# Rocket_End.net
KiCad netlist of a schematic drawn in EAGLE
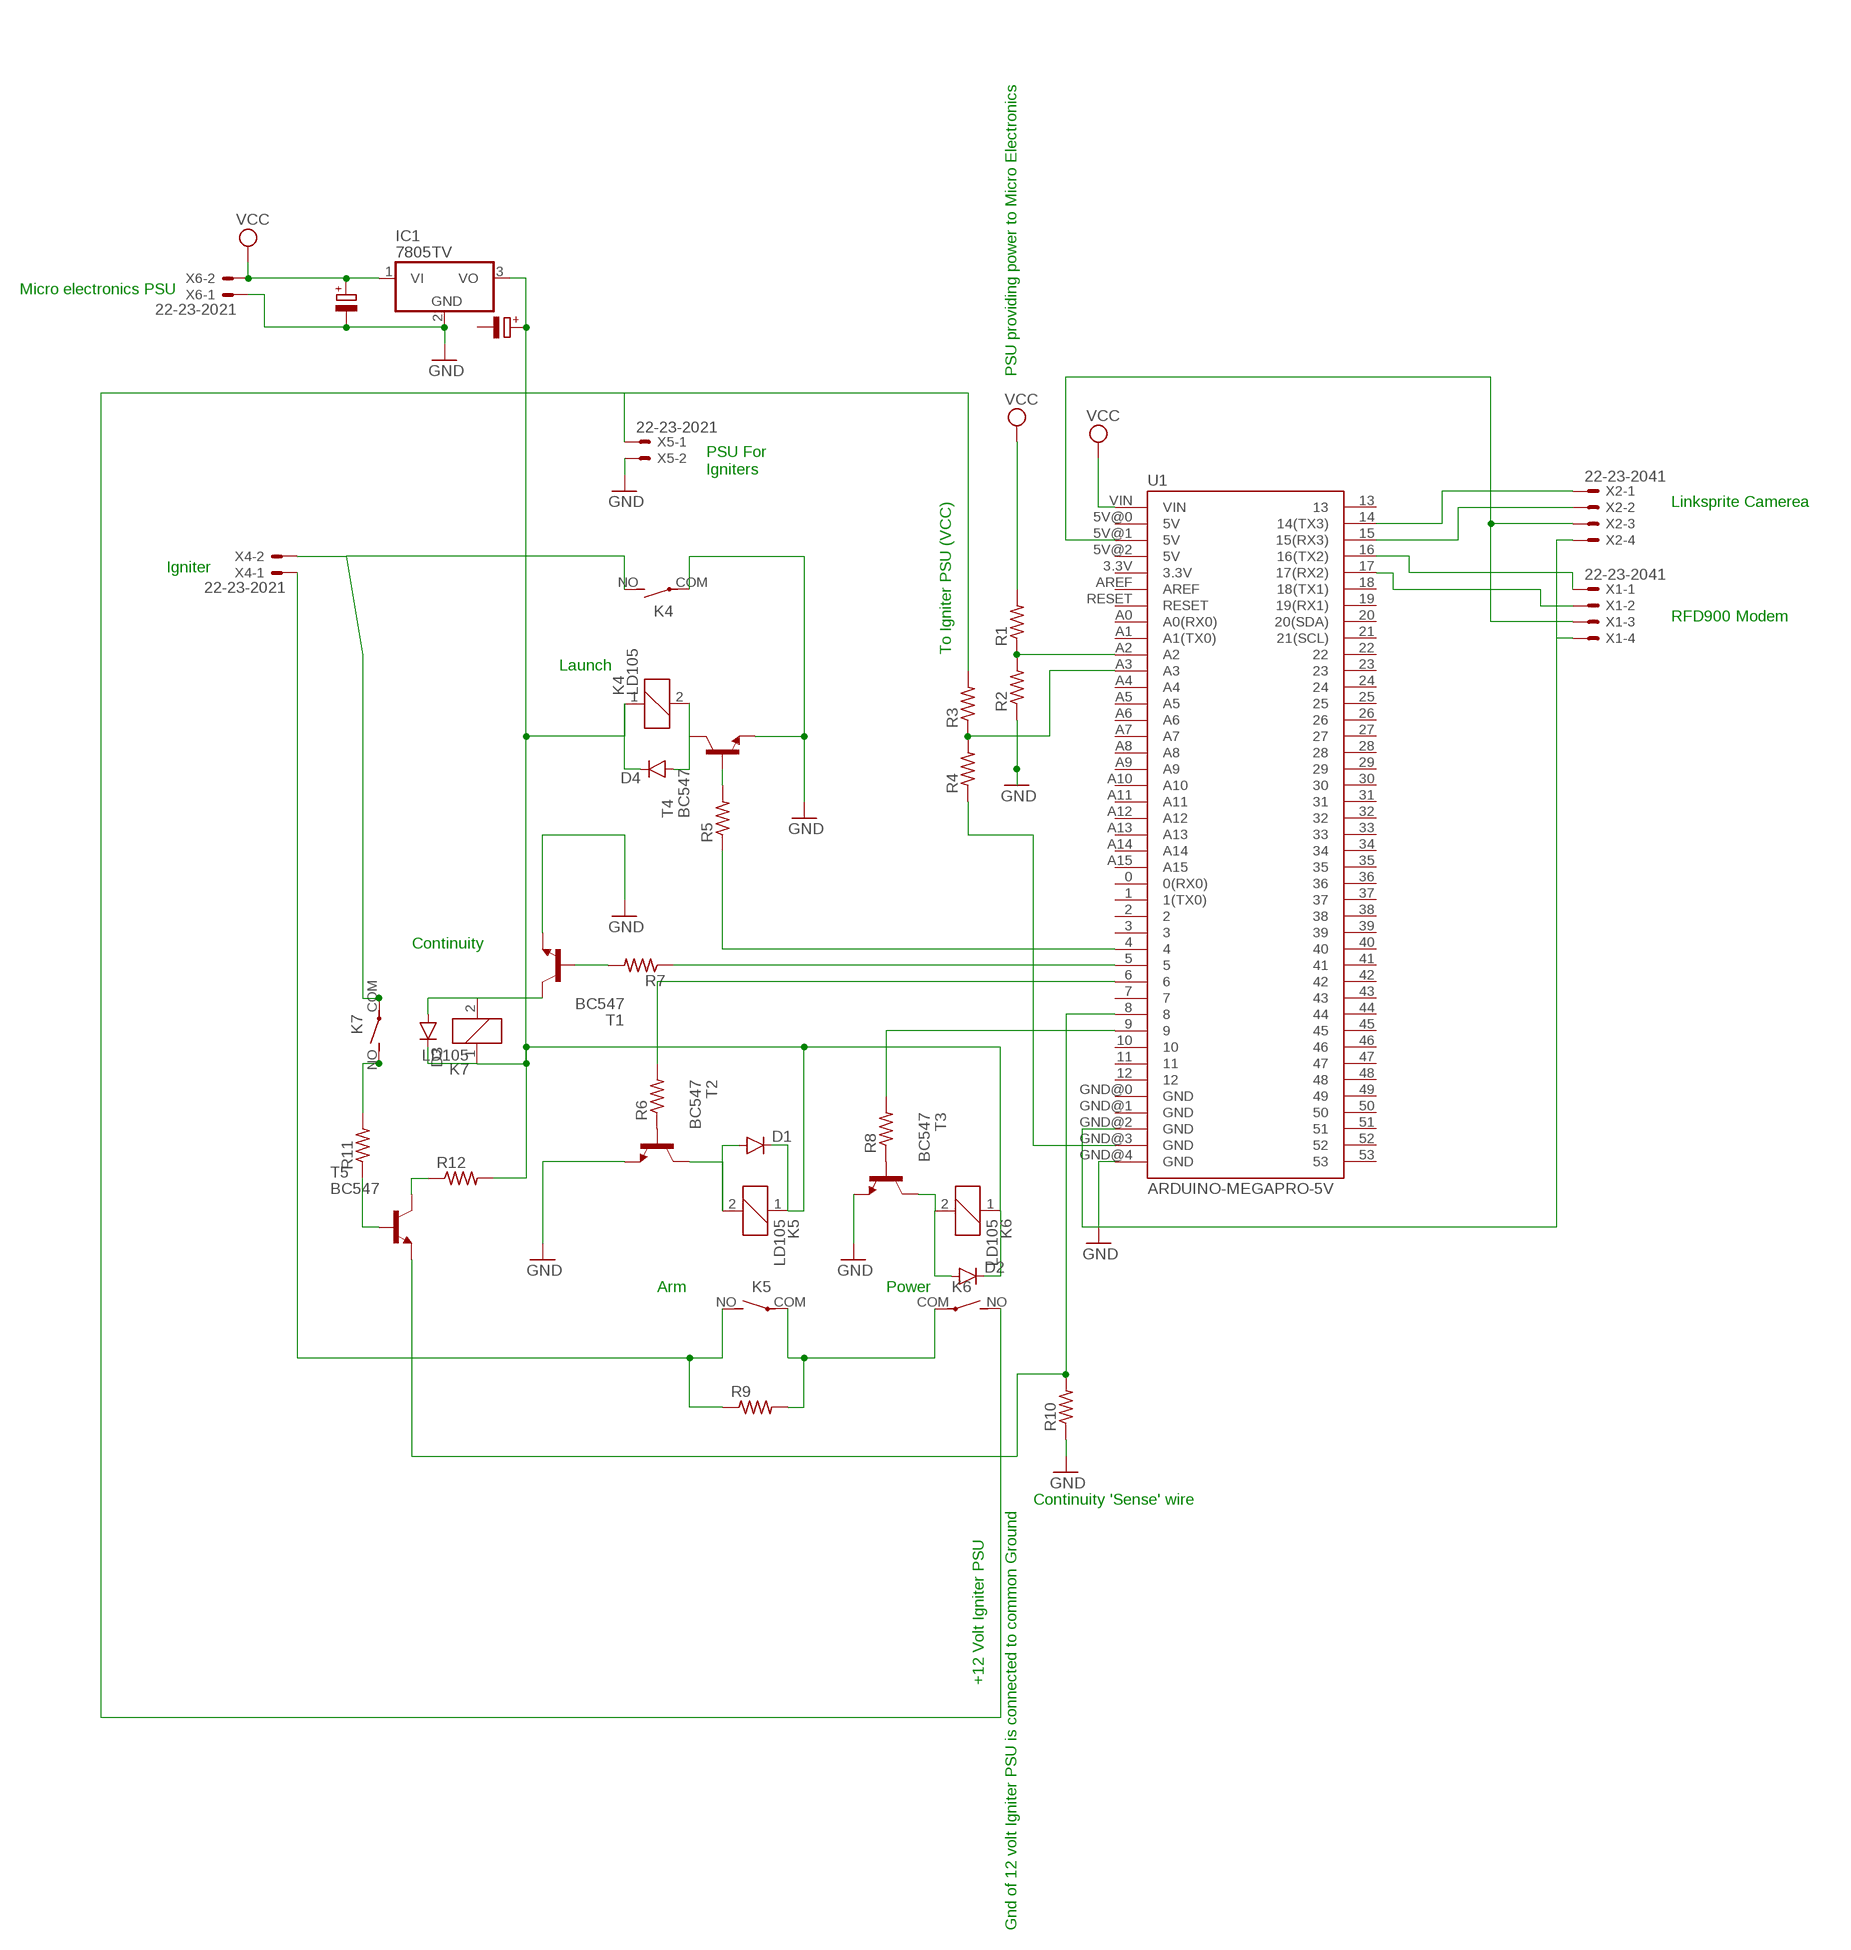
[diagram p0: schematic, sheet 1]

(export (version "E")
  (design (tool "Eeschema 10.0.6"))
  (components
    (comp (ref "D1")
      (value "DIODE1N4148")
      (footprint "eagle-import:DIODE-1N4148")
      (libsource (lib "eagle-import") (part "DIODE1N4148"))
    )
    (comp (ref "D2")
      (value "DIODE1N4148")
      (footprint "eagle-import:DIODE-1N4148")
      (libsource (lib "eagle-import") (part "DIODE1N4148"))
    )
    (comp (ref "D3")
      (value "DIODE1N4148")
      (footprint "eagle-import:DIODE-1N4148")
      (libsource (lib "eagle-import") (part "DIODE1N4148"))
    )
    (comp (ref "D4")
      (value "DIODE1N4148")
      (footprint "eagle-import:DIODE-1N4148")
      (libsource (lib "eagle-import") (part "DIODE1N4148"))
    )
    (comp (ref "IC1")
      (value "7805TV")
      (footprint "eagle-import:TO220V")
      (libsource (lib "eagle-import") (part "78TV05"))
    )
    (comp (ref "K4")
      (value "LD105")
      (footprint "eagle-import:LD")
      (libsource (lib "eagle-import") (part "LD?105"))
    )
    (comp (ref "K5")
      (value "LD105")
      (footprint "eagle-import:LD")
      (libsource (lib "eagle-import") (part "LD?105"))
    )
    (comp (ref "K6")
      (value "LD105")
      (footprint "eagle-import:LD")
      (libsource (lib "eagle-import") (part "LD?105"))
    )
    (comp (ref "K7")
      (value "LD105")
      (footprint "eagle-import:LD")
      (libsource (lib "eagle-import") (part "LD?105"))
    )
    (comp (ref "R1")
      (value "R-US_0204/7")
      (footprint "eagle-import:0204_7")
      (libsource (lib "eagle-import") (part "R-US_0204/7"))
    )
    (comp (ref "R2")
      (value "R-US_0204/7")
      (footprint "eagle-import:0204_7")
      (libsource (lib "eagle-import") (part "R-US_0204/7"))
    )
    (comp (ref "R3")
      (value "R-US_0204/7")
      (footprint "eagle-import:0204_7")
      (libsource (lib "eagle-import") (part "R-US_0204/7"))
    )
    (comp (ref "R4")
      (value "R-US_0204/7")
      (footprint "eagle-import:0204_7")
      (libsource (lib "eagle-import") (part "R-US_0204/7"))
    )
    (comp (ref "R5")
      (value "R-US_0204/7")
      (footprint "eagle-import:0204_7")
      (libsource (lib "eagle-import") (part "resistor_R-US_0204/7"))
    )
    (comp (ref "R6")
      (value "R-US_0204/7")
      (footprint "eagle-import:0204_7")
      (libsource (lib "eagle-import") (part "resistor_R-US_0204/7"))
    )
    (comp (ref "R7")
      (value "R-US_0204/7")
      (footprint "eagle-import:0204_7")
      (libsource (lib "eagle-import") (part "resistor_R-US_0204/7"))
    )
    (comp (ref "R8")
      (value "R-US_0204/7")
      (footprint "eagle-import:0204_7")
      (libsource (lib "eagle-import") (part "resistor_R-US_0204/7"))
    )
    (comp (ref "R9")
      (value "R-US_0204/7")
      (footprint "eagle-import:0204_7")
      (libsource (lib "eagle-import") (part "R-US_0204/7"))
    )
    (comp (ref "R10")
      (value "R-US_0207/7")
      (footprint "eagle-import:0207_7")
      (libsource (lib "eagle-import") (part "resistor_R-US_0207/7"))
    )
    (comp (ref "R11")
      (value "R-US_0204/7")
      (footprint "eagle-import:0204_7")
      (libsource (lib "eagle-import") (part "R-US_0204/7"))
    )
    (comp (ref "R12")
      (value "R-US_0204/7")
      (footprint "eagle-import:0204_7")
      (libsource (lib "eagle-import") (part "resistor_R-US_0204/7"))
    )
    (comp (ref "T1")
      (value "BC547")
      (footprint "eagle-import:TO92")
      (libsource (lib "eagle-import") (part "transistor-neu-to92_BC547"))
    )
    (comp (ref "T2")
      (value "BC547")
      (footprint "eagle-import:TO92")
      (libsource (lib "eagle-import") (part "transistor-neu-to92_BC547"))
    )
    (comp (ref "T3")
      (value "BC547")
      (footprint "eagle-import:TO92")
      (libsource (lib "eagle-import") (part "transistor-neu-to92_BC547"))
    )
    (comp (ref "T4")
      (value "BC547")
      (footprint "eagle-import:TO92")
      (libsource (lib "eagle-import") (part "transistor-neu-to92_BC547"))
    )
    (comp (ref "T5")
      (value "BC547")
      (footprint "eagle-import:TO92")
      (libsource (lib "eagle-import") (part "BC547"))
    )
    (comp (ref "U1")
      (value "ARDUINO-MEGAPRO-5V")
      (footprint "eagle-import:ARDUINO_MEGA-PRO-5V")
      (libsource (lib "eagle-import") (part "ARDUINO-MEGAPRO-5V"))
    )
    (comp (ref "X1")
      (value "22-23-2041")
      (footprint "eagle-import:22-23-2041")
      (fields (field (name "MF") "MOLEX"))
      (libsource (lib "eagle-import") (part "22-23-2041"))
    )
    (comp (ref "X2")
      (value "22-23-2041")
      (footprint "eagle-import:22-23-2041")
      (fields (field (name "MF") "MOLEX"))
      (libsource (lib "eagle-import") (part "22-23-2041"))
    )
    (comp (ref "X4")
      (value "22-23-2021")
      (footprint "eagle-import:22-23-2021")
      (fields (field (name "MF") "MOLEX"))
      (libsource (lib "eagle-import") (part "22-23-2021"))
    )
    (comp (ref "X5")
      (value "22-23-2021")
      (footprint "eagle-import:22-23-2021")
      (fields (field (name "MF") "MOLEX"))
      (libsource (lib "eagle-import") (part "22-23-2021"))
    )
    (comp (ref "X6")
      (value "22-23-2021")
      (footprint "eagle-import:22-23-2021")
      (fields (field (name "MF") "MOLEX"))
      (libsource (lib "eagle-import") (part "22-23-2021"))
    )
  )
  (nets
    (net (code "1") (name "GND") (class "Default")
      (node (ref "IC1") (pin "2") (pinfunction "GND_2") (pintype "passive"))
      (node (ref "K4") (pin "COM") (pinfunction "P_COM") (pintype "passive"))
      (node (ref "R10") (pin "1") (pinfunction "1_1") (pintype "passive"))
      (node (ref "R2") (pin "1") (pinfunction "1_1") (pintype "passive"))
      (node (ref "T1") (pin "1") (pinfunction "E_1") (pintype "passive"))
      (node (ref "T2") (pin "1") (pinfunction "E_1") (pintype "passive"))
      (node (ref "T3") (pin "1") (pinfunction "E_1") (pintype "passive"))
      (node (ref "T4") (pin "1") (pinfunction "E_1") (pintype "passive"))
      (node (ref "U1") (pin "GND@4") (pinfunction "GND_GND@4") (pintype "bidirectional"))
      (node (ref "X5") (pin "2") (pinfunction "S_2") (pintype "passive"))
      (node (ref "X6") (pin "1") (pinfunction "S_1") (pintype "passive"))
    )
    (net (code "2") (name "Net-(IC1-VO)") (class "Default")
      (node (ref "D1") (pin "C") (pinfunction "C_C") (pintype "passive"))
      (node (ref "D2") (pin "C") (pinfunction "C_C") (pintype "passive"))
      (node (ref "D3") (pin "C") (pinfunction "C_C") (pintype "passive"))
      (node (ref "D4") (pin "C") (pinfunction "C_C") (pintype "passive"))
      (node (ref "IC1") (pin "3") (pinfunction "VO_3") (pintype "passive"))
      (node (ref "K4") (pin "1") (pinfunction "1_1") (pintype "passive"))
      (node (ref "K5") (pin "1") (pinfunction "1_1") (pintype "passive"))
      (node (ref "K6") (pin "1") (pinfunction "1_1") (pintype "passive"))
      (node (ref "K7") (pin "1") (pinfunction "1_1") (pintype "passive"))
      (node (ref "R12") (pin "2") (pinfunction "2_2") (pintype "passive"))
    )
    (net (code "3") (name "Net-(K4B-S)") (class "Default")
      (node (ref "K4") (pin "NO") (pinfunction "S_NO") (pintype "passive"))
      (node (ref "K7") (pin "COM") (pinfunction "P_COM") (pintype "passive"))
      (node (ref "X4") (pin "2") (pinfunction "S_2") (pintype "passive"))
    )
    (net (code "4") (name "Net-(K5B-P)") (class "Default")
      (node (ref "K5") (pin "COM") (pinfunction "P_COM") (pintype "passive"))
      (node (ref "K6") (pin "COM") (pinfunction "P_COM") (pintype "passive"))
      (node (ref "R9") (pin "2") (pinfunction "2_2") (pintype "passive"))
    )
    (net (code "5") (name "Net-(K5B-S)") (class "Default")
      (node (ref "K5") (pin "NO") (pinfunction "S_NO") (pintype "passive"))
      (node (ref "R9") (pin "1") (pinfunction "1_1") (pintype "passive"))
      (node (ref "X4") (pin "1") (pinfunction "S_1") (pintype "passive"))
    )
    (net (code "6") (name "Net-(K6B-S)") (class "Default")
      (node (ref "K6") (pin "NO") (pinfunction "S_NO") (pintype "passive"))
      (node (ref "R3") (pin "2") (pinfunction "2_2") (pintype "passive"))
      (node (ref "X5") (pin "1") (pinfunction "S_1") (pintype "passive"))
    )
    (net (code "7") (name "Net-(K7B-S)") (class "Default")
      (node (ref "K7") (pin "NO") (pinfunction "S_NO") (pintype "passive"))
      (node (ref "R11") (pin "2") (pinfunction "2_2") (pintype "passive"))
    )
    (net (code "8") (name "Net-(R1-Pad1)") (class "Default")
      (node (ref "R1") (pin "1") (pinfunction "1_1") (pintype "passive"))
      (node (ref "R2") (pin "2") (pinfunction "2_2") (pintype "passive"))
      (node (ref "U1") (pin "A2") (pinfunction "A2_A2") (pintype "bidirectional"))
    )
    (net (code "9") (name "Net-(R3-Pad1)") (class "Default")
      (node (ref "R3") (pin "1") (pinfunction "1_1") (pintype "passive"))
      (node (ref "R4") (pin "2") (pinfunction "2_2") (pintype "passive"))
      (node (ref "U1") (pin "A3") (pinfunction "A3_A3") (pintype "bidirectional"))
    )
    (net (code "10") (name "Net-(R4-Pad1)") (class "Default")
      (node (ref "R4") (pin "1") (pinfunction "1_1") (pintype "passive"))
      (node (ref "U1") (pin "GND@3") (pinfunction "GND_GND@3") (pintype "bidirectional"))
    )
    (net (code "11") (name "Net-(R5-Pad1)") (class "Default")
      (node (ref "R5") (pin "1") (pinfunction "1_1") (pintype "passive"))
      (node (ref "U1") (pin "4") (pinfunction "4_4") (pintype "bidirectional"))
    )
    (net (code "12") (name "Net-(R6-Pad2)") (class "Default")
      (node (ref "R6") (pin "2") (pinfunction "2_2") (pintype "passive"))
      (node (ref "U1") (pin "6") (pinfunction "6_6") (pintype "bidirectional"))
    )
    (net (code "13") (name "Net-(R7-Pad1)") (class "Default")
      (node (ref "R7") (pin "1") (pinfunction "1_1") (pintype "passive"))
      (node (ref "U1") (pin "5") (pinfunction "5_5") (pintype "bidirectional"))
    )
    (net (code "14") (name "Net-(R8-Pad2)") (class "Default")
      (node (ref "R8") (pin "2") (pinfunction "2_2") (pintype "passive"))
      (node (ref "U1") (pin "9") (pinfunction "9_9") (pintype "bidirectional"))
    )
    (net (code "15") (name "Net-(T1-B)") (class "Default")
      (node (ref "R7") (pin "2") (pinfunction "2_2") (pintype "passive"))
      (node (ref "T1") (pin "2") (pinfunction "B_2") (pintype "passive"))
    )
    (net (code "16") (name "Net-(T1-C)") (class "Default")
      (node (ref "D3") (pin "A") (pinfunction "A_A") (pintype "passive"))
      (node (ref "K7") (pin "2") (pinfunction "2_2") (pintype "passive"))
      (node (ref "T1") (pin "3") (pinfunction "C_3") (pintype "passive"))
    )
    (net (code "17") (name "Net-(T2-B)") (class "Default")
      (node (ref "R6") (pin "1") (pinfunction "1_1") (pintype "passive"))
      (node (ref "T2") (pin "2") (pinfunction "B_2") (pintype "passive"))
    )
    (net (code "18") (name "Net-(T2-C)") (class "Default")
      (node (ref "D1") (pin "A") (pinfunction "A_A") (pintype "passive"))
      (node (ref "K5") (pin "2") (pinfunction "2_2") (pintype "passive"))
      (node (ref "T2") (pin "3") (pinfunction "C_3") (pintype "passive"))
    )
    (net (code "19") (name "Net-(T3-B)") (class "Default")
      (node (ref "R8") (pin "1") (pinfunction "1_1") (pintype "passive"))
      (node (ref "T3") (pin "2") (pinfunction "B_2") (pintype "passive"))
    )
    (net (code "20") (name "Net-(T3-C)") (class "Default")
      (node (ref "D2") (pin "A") (pinfunction "A_A") (pintype "passive"))
      (node (ref "K6") (pin "2") (pinfunction "2_2") (pintype "passive"))
      (node (ref "T3") (pin "3") (pinfunction "C_3") (pintype "passive"))
    )
    (net (code "21") (name "Net-(T4-B)") (class "Default")
      (node (ref "R5") (pin "2") (pinfunction "2_2") (pintype "passive"))
      (node (ref "T4") (pin "2") (pinfunction "B_2") (pintype "passive"))
    )
    (net (code "22") (name "Net-(T4-C)") (class "Default")
      (node (ref "D4") (pin "A") (pinfunction "A_A") (pintype "passive"))
      (node (ref "K4") (pin "2") (pinfunction "2_2") (pintype "passive"))
      (node (ref "T4") (pin "3") (pinfunction "C_3") (pintype "passive"))
    )
    (net (code "23") (name "Net-(T5-B)") (class "Default")
      (node (ref "R11") (pin "1") (pinfunction "1_1") (pintype "passive"))
      (node (ref "T5") (pin "2") (pinfunction "B_2") (pintype "passive"))
    )
    (net (code "24") (name "Net-(T5-C)") (class "Default")
      (node (ref "R12") (pin "1") (pinfunction "1_1") (pintype "passive"))
      (node (ref "T5") (pin "3") (pinfunction "C_3") (pintype "passive"))
    )
    (net (code "25") (name "Net-(T5-E)") (class "Default")
      (node (ref "R10") (pin "2") (pinfunction "2_2") (pintype "passive"))
      (node (ref "T5") (pin "1") (pinfunction "E_1") (pintype "passive"))
      (node (ref "U1") (pin "8") (pinfunction "8_8") (pintype "bidirectional"))
    )
    (net (code "26") (name "Net-(U1-14(TX3))") (class "Default")
      (node (ref "U1") (pin "14") (pinfunction "14(TX3)_14") (pintype "bidirectional"))
      (node (ref "X2") (pin "1") (pinfunction "S_1") (pintype "passive"))
    )
    (net (code "27") (name "Net-(U1-15(RX3))") (class "Default")
      (node (ref "U1") (pin "15") (pinfunction "15(RX3)_15") (pintype "bidirectional"))
      (node (ref "X2") (pin "2") (pinfunction "S_2") (pintype "passive"))
    )
    (net (code "28") (name "Net-(U1-16(TX2))") (class "Default")
      (node (ref "U1") (pin "16") (pinfunction "16(TX2)_16") (pintype "bidirectional"))
      (node (ref "X1") (pin "1") (pinfunction "S_1") (pintype "passive"))
    )
    (net (code "29") (name "Net-(U1-17(RX2))") (class "Default")
      (node (ref "U1") (pin "17") (pinfunction "17(RX2)_17") (pintype "bidirectional"))
      (node (ref "X1") (pin "2") (pinfunction "S_2") (pintype "passive"))
    )
    (net (code "30") (name "Net-(X1C-S)") (class "Default")
      (node (ref "U1") (pin "5V@1") (pinfunction "5V_5V@1") (pintype "bidirectional"))
      (node (ref "X1") (pin "3") (pinfunction "S_3") (pintype "passive"))
      (node (ref "X2") (pin "3") (pinfunction "S_3") (pintype "passive"))
    )
    (net (code "31") (name "Net-(X1D-S)") (class "Default")
      (node (ref "U1") (pin "GND@2") (pinfunction "GND_GND@2") (pintype "bidirectional"))
      (node (ref "X1") (pin "4") (pinfunction "S_4") (pintype "passive"))
      (node (ref "X2") (pin "4") (pinfunction "S_4") (pintype "passive"))
    )
    (net (code "32") (name "VCC") (class "Default")
      (node (ref "IC1") (pin "1") (pinfunction "VI_1") (pintype "input"))
      (node (ref "R1") (pin "2") (pinfunction "2_2") (pintype "passive"))
      (node (ref "U1") (pin "VIN") (pinfunction "VIN_VIN") (pintype "bidirectional"))
      (node (ref "X6") (pin "2") (pinfunction "S_2") (pintype "passive"))
    )
    (net (code "33") (name "unconnected-(U1-0(RX0)-Pad0)") (class "Default")
      (node (ref "U1") (pin "0") (pinfunction "0(RX0)_0") (pintype "bidirectional"))
    )
    (net (code "34") (name "unconnected-(U1-1(TX0)-Pad1)") (class "Default")
      (node (ref "U1") (pin "1") (pinfunction "1(TX0)_1") (pintype "bidirectional"))
    )
    (net (code "35") (name "unconnected-(U1-5V-Pad5V@0)") (class "Default")
      (node (ref "U1") (pin "5V@0") (pinfunction "5V_5V@0") (pintype "bidirectional"))
    )
    (net (code "36") (name "unconnected-(U1-5V-Pad5V@2)") (class "Default")
      (node (ref "U1") (pin "5V@2") (pinfunction "5V_5V@2") (pintype "bidirectional"))
    )
    (net (code "37") (name "unconnected-(U1-18(TX1)-Pad18)") (class "Default")
      (node (ref "U1") (pin "18") (pinfunction "18(TX1)_18") (pintype "bidirectional"))
    )
    (net (code "38") (name "unconnected-(U1-19(RX1)-Pad19)") (class "Default")
      (node (ref "U1") (pin "19") (pinfunction "19(RX1)_19") (pintype "bidirectional"))
    )
    (net (code "39") (name "unconnected-(U1-20(SDA)-Pad20)") (class "Default")
      (node (ref "U1") (pin "20") (pinfunction "20(SDA)_20") (pintype "bidirectional"))
    )
    (net (code "40") (name "unconnected-(U1-21(SCL)-Pad21)") (class "Default")
      (node (ref "U1") (pin "21") (pinfunction "21(SCL)_21") (pintype "bidirectional"))
    )
    (net (code "41") (name "unconnected-(U1-A0(RX0)-PadA0)") (class "Default")
      (node (ref "U1") (pin "A0") (pinfunction "A0(RX0)_A0") (pintype "bidirectional"))
    )
    (net (code "42") (name "unconnected-(U1-A1(TX0)-PadA1)") (class "Default")
      (node (ref "U1") (pin "A1") (pinfunction "A1(TX0)_A1") (pintype "bidirectional"))
    )
    (net (code "43") (name "unconnected-(U1-GND-PadGND@0)") (class "Default")
      (node (ref "U1") (pin "GND@0") (pinfunction "GND_GND@0") (pintype "bidirectional"))
    )
    (net (code "44") (name "unconnected-(U1-GND-PadGND@1)") (class "Default")
      (node (ref "U1") (pin "GND@1") (pinfunction "GND_GND@1") (pintype "bidirectional"))
    )
    (net (code "45") (name "unconnected-(U1-Pad2)") (class "Default")
      (node (ref "U1") (pin "2") (pinfunction "2_2") (pintype "bidirectional"))
    )
    (net (code "46") (name "unconnected-(U1-Pad3)") (class "Default")
      (node (ref "U1") (pin "3") (pinfunction "3_3") (pintype "bidirectional"))
    )
    (net (code "47") (name "unconnected-(U1-Pad3.3V)") (class "Default")
      (node (ref "U1") (pin "3.3V") (pinfunction "3.3V_3.3V") (pintype "bidirectional"))
    )
    (net (code "48") (name "unconnected-(U1-Pad7)") (class "Default")
      (node (ref "U1") (pin "7") (pinfunction "7_7") (pintype "bidirectional"))
    )
    (net (code "49") (name "unconnected-(U1-Pad10)") (class "Default")
      (node (ref "U1") (pin "10") (pinfunction "10_10") (pintype "bidirectional"))
    )
    (net (code "50") (name "unconnected-(U1-Pad11)") (class "Default")
      (node (ref "U1") (pin "11") (pinfunction "11_11") (pintype "bidirectional"))
    )
    (net (code "51") (name "unconnected-(U1-Pad12)") (class "Default")
      (node (ref "U1") (pin "12") (pinfunction "12_12") (pintype "bidirectional"))
    )
    (net (code "52") (name "unconnected-(U1-Pad13)") (class "Default")
      (node (ref "U1") (pin "13") (pinfunction "13_13") (pintype "bidirectional"))
    )
    (net (code "53") (name "unconnected-(U1-Pad22)") (class "Default")
      (node (ref "U1") (pin "22") (pinfunction "22_22") (pintype "bidirectional"))
    )
    (net (code "54") (name "unconnected-(U1-Pad23)") (class "Default")
      (node (ref "U1") (pin "23") (pinfunction "23_23") (pintype "bidirectional"))
    )
    (net (code "55") (name "unconnected-(U1-Pad24)") (class "Default")
      (node (ref "U1") (pin "24") (pinfunction "24_24") (pintype "bidirectional"))
    )
    (net (code "56") (name "unconnected-(U1-Pad25)") (class "Default")
      (node (ref "U1") (pin "25") (pinfunction "25_25") (pintype "bidirectional"))
    )
    (net (code "57") (name "unconnected-(U1-Pad26)") (class "Default")
      (node (ref "U1") (pin "26") (pinfunction "26_26") (pintype "bidirectional"))
    )
    (net (code "58") (name "unconnected-(U1-Pad27)") (class "Default")
      (node (ref "U1") (pin "27") (pinfunction "27_27") (pintype "bidirectional"))
    )
    (net (code "59") (name "unconnected-(U1-Pad28)") (class "Default")
      (node (ref "U1") (pin "28") (pinfunction "28_28") (pintype "bidirectional"))
    )
    (net (code "60") (name "unconnected-(U1-Pad29)") (class "Default")
      (node (ref "U1") (pin "29") (pinfunction "29_29") (pintype "bidirectional"))
    )
    (net (code "61") (name "unconnected-(U1-Pad30)") (class "Default")
      (node (ref "U1") (pin "30") (pinfunction "30_30") (pintype "bidirectional"))
    )
    (net (code "62") (name "unconnected-(U1-Pad31)") (class "Default")
      (node (ref "U1") (pin "31") (pinfunction "31_31") (pintype "bidirectional"))
    )
    (net (code "63") (name "unconnected-(U1-Pad32)") (class "Default")
      (node (ref "U1") (pin "32") (pinfunction "32_32") (pintype "bidirectional"))
    )
    (net (code "64") (name "unconnected-(U1-Pad33)") (class "Default")
      (node (ref "U1") (pin "33") (pinfunction "33_33") (pintype "bidirectional"))
    )
    (net (code "65") (name "unconnected-(U1-Pad34)") (class "Default")
      (node (ref "U1") (pin "34") (pinfunction "34_34") (pintype "bidirectional"))
    )
    (net (code "66") (name "unconnected-(U1-Pad35)") (class "Default")
      (node (ref "U1") (pin "35") (pinfunction "35_35") (pintype "bidirectional"))
    )
    (net (code "67") (name "unconnected-(U1-Pad36)") (class "Default")
      (node (ref "U1") (pin "36") (pinfunction "36_36") (pintype "bidirectional"))
    )
    (net (code "68") (name "unconnected-(U1-Pad37)") (class "Default")
      (node (ref "U1") (pin "37") (pinfunction "37_37") (pintype "bidirectional"))
    )
    (net (code "69") (name "unconnected-(U1-Pad38)") (class "Default")
      (node (ref "U1") (pin "38") (pinfunction "38_38") (pintype "bidirectional"))
    )
    (net (code "70") (name "unconnected-(U1-Pad39)") (class "Default")
      (node (ref "U1") (pin "39") (pinfunction "39_39") (pintype "bidirectional"))
    )
    (net (code "71") (name "unconnected-(U1-Pad40)") (class "Default")
      (node (ref "U1") (pin "40") (pinfunction "40_40") (pintype "bidirectional"))
    )
    (net (code "72") (name "unconnected-(U1-Pad41)") (class "Default")
      (node (ref "U1") (pin "41") (pinfunction "41_41") (pintype "bidirectional"))
    )
    (net (code "73") (name "unconnected-(U1-Pad42)") (class "Default")
      (node (ref "U1") (pin "42") (pinfunction "42_42") (pintype "bidirectional"))
    )
    (net (code "74") (name "unconnected-(U1-Pad43)") (class "Default")
      (node (ref "U1") (pin "43") (pinfunction "43_43") (pintype "bidirectional"))
    )
    (net (code "75") (name "unconnected-(U1-Pad44)") (class "Default")
      (node (ref "U1") (pin "44") (pinfunction "44_44") (pintype "bidirectional"))
    )
    (net (code "76") (name "unconnected-(U1-Pad45)") (class "Default")
      (node (ref "U1") (pin "45") (pinfunction "45_45") (pintype "bidirectional"))
    )
    (net (code "77") (name "unconnected-(U1-Pad46)") (class "Default")
      (node (ref "U1") (pin "46") (pinfunction "46_46") (pintype "bidirectional"))
    )
    (net (code "78") (name "unconnected-(U1-Pad47)") (class "Default")
      (node (ref "U1") (pin "47") (pinfunction "47_47") (pintype "bidirectional"))
    )
    (net (code "79") (name "unconnected-(U1-Pad48)") (class "Default")
      (node (ref "U1") (pin "48") (pinfunction "48_48") (pintype "bidirectional"))
    )
    (net (code "80") (name "unconnected-(U1-Pad49)") (class "Default")
      (node (ref "U1") (pin "49") (pinfunction "49_49") (pintype "bidirectional"))
    )
    (net (code "81") (name "unconnected-(U1-Pad50)") (class "Default")
      (node (ref "U1") (pin "50") (pinfunction "50_50") (pintype "bidirectional"))
    )
    (net (code "82") (name "unconnected-(U1-Pad51)") (class "Default")
      (node (ref "U1") (pin "51") (pinfunction "51_51") (pintype "bidirectional"))
    )
    (net (code "83") (name "unconnected-(U1-Pad52)") (class "Default")
      (node (ref "U1") (pin "52") (pinfunction "52_52") (pintype "bidirectional"))
    )
    (net (code "84") (name "unconnected-(U1-Pad53)") (class "Default")
      (node (ref "U1") (pin "53") (pinfunction "53_53") (pintype "bidirectional"))
    )
    (net (code "85") (name "unconnected-(U1-PadA4)") (class "Default")
      (node (ref "U1") (pin "A4") (pinfunction "A4_A4") (pintype "bidirectional"))
    )
    (net (code "86") (name "unconnected-(U1-PadA5)") (class "Default")
      (node (ref "U1") (pin "A5") (pinfunction "A5_A5") (pintype "bidirectional"))
    )
    (net (code "87") (name "unconnected-(U1-PadA6)") (class "Default")
      (node (ref "U1") (pin "A6") (pinfunction "A6_A6") (pintype "bidirectional"))
    )
    (net (code "88") (name "unconnected-(U1-PadA7)") (class "Default")
      (node (ref "U1") (pin "A7") (pinfunction "A7_A7") (pintype "bidirectional"))
    )
    (net (code "89") (name "unconnected-(U1-PadA8)") (class "Default")
      (node (ref "U1") (pin "A8") (pinfunction "A8_A8") (pintype "bidirectional"))
    )
    (net (code "90") (name "unconnected-(U1-PadA9)") (class "Default")
      (node (ref "U1") (pin "A9") (pinfunction "A9_A9") (pintype "bidirectional"))
    )
    (net (code "91") (name "unconnected-(U1-PadA10)") (class "Default")
      (node (ref "U1") (pin "A10") (pinfunction "A10_A10") (pintype "bidirectional"))
    )
    (net (code "92") (name "unconnected-(U1-PadA11)") (class "Default")
      (node (ref "U1") (pin "A11") (pinfunction "A11_A11") (pintype "bidirectional"))
    )
    (net (code "93") (name "unconnected-(U1-PadA12)") (class "Default")
      (node (ref "U1") (pin "A12") (pinfunction "A12_A12") (pintype "bidirectional"))
    )
    (net (code "94") (name "unconnected-(U1-PadA13)") (class "Default")
      (node (ref "U1") (pin "A13") (pinfunction "A13_A13") (pintype "bidirectional"))
    )
    (net (code "95") (name "unconnected-(U1-PadA14)") (class "Default")
      (node (ref "U1") (pin "A14") (pinfunction "A14_A14") (pintype "bidirectional"))
    )
    (net (code "96") (name "unconnected-(U1-PadA15)") (class "Default")
      (node (ref "U1") (pin "A15") (pinfunction "A15_A15") (pintype "bidirectional"))
    )
    (net (code "97") (name "unconnected-(U1-PadAREF)") (class "Default")
      (node (ref "U1") (pin "AREF") (pinfunction "AREF_AREF") (pintype "bidirectional"))
    )
    (net (code "98") (name "unconnected-(U1-PadRESET)") (class "Default")
      (node (ref "U1") (pin "RESET") (pinfunction "RESET_RESET") (pintype "bidirectional"))
    )
  )
)
